# 08_-CAN_INTERPOSER.net
KiCad netlist of a schematic drawn in Altium Designer
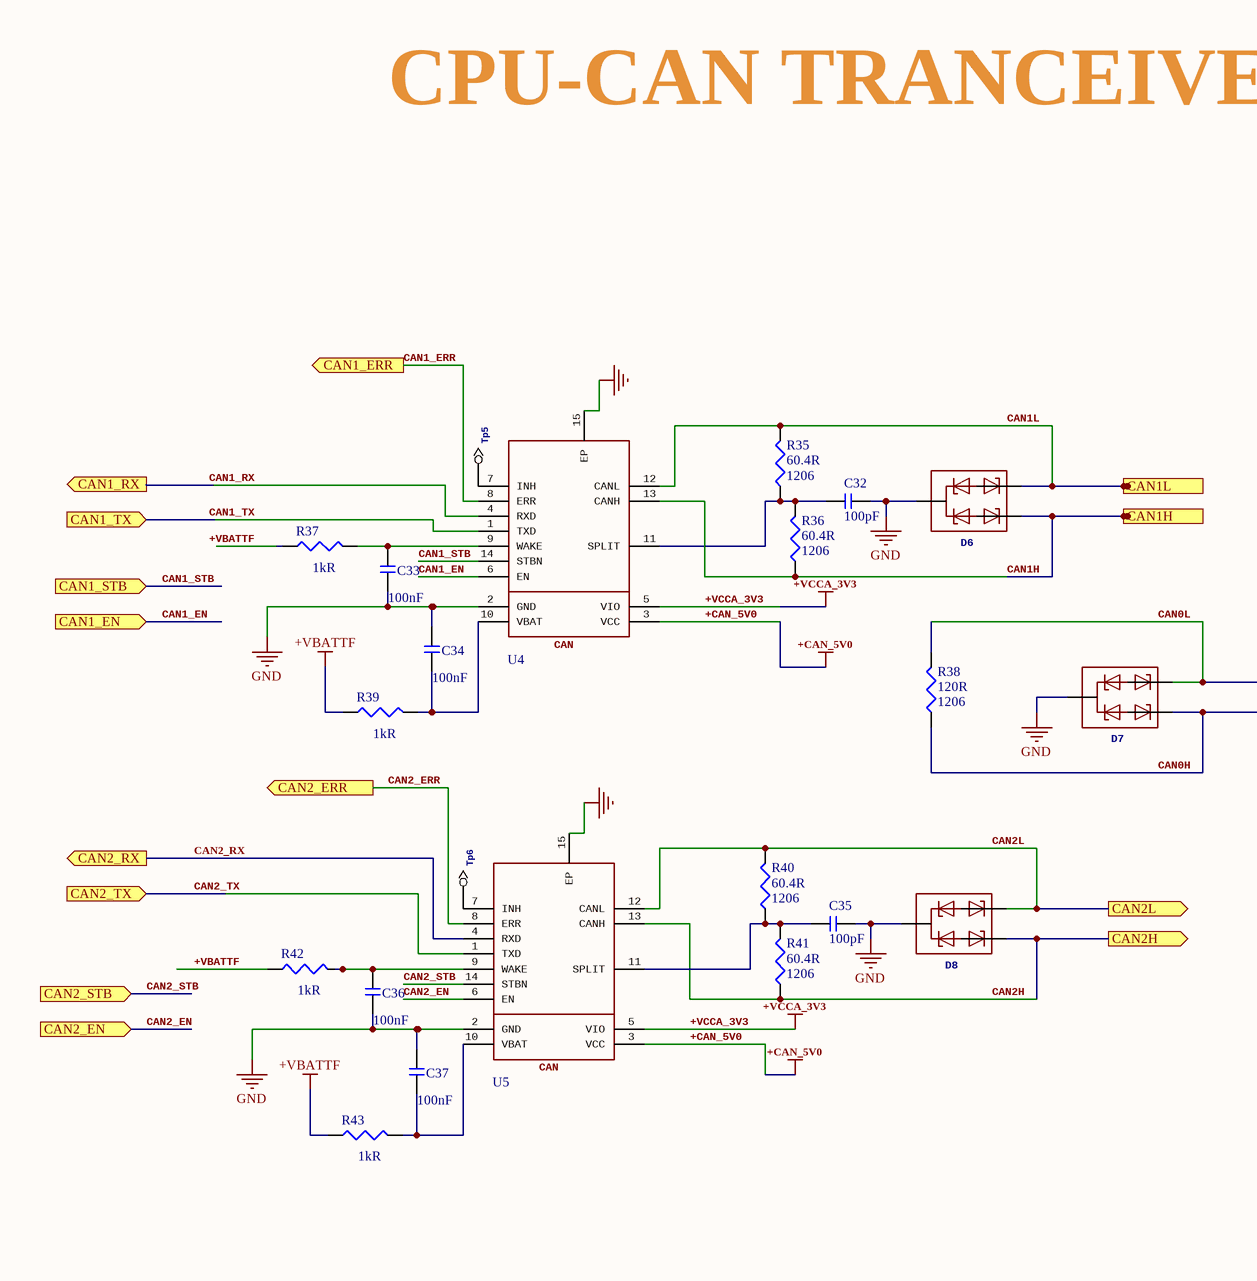
[diagram p0: [08]-CAN,INTERPOSER.SchDoc, left]
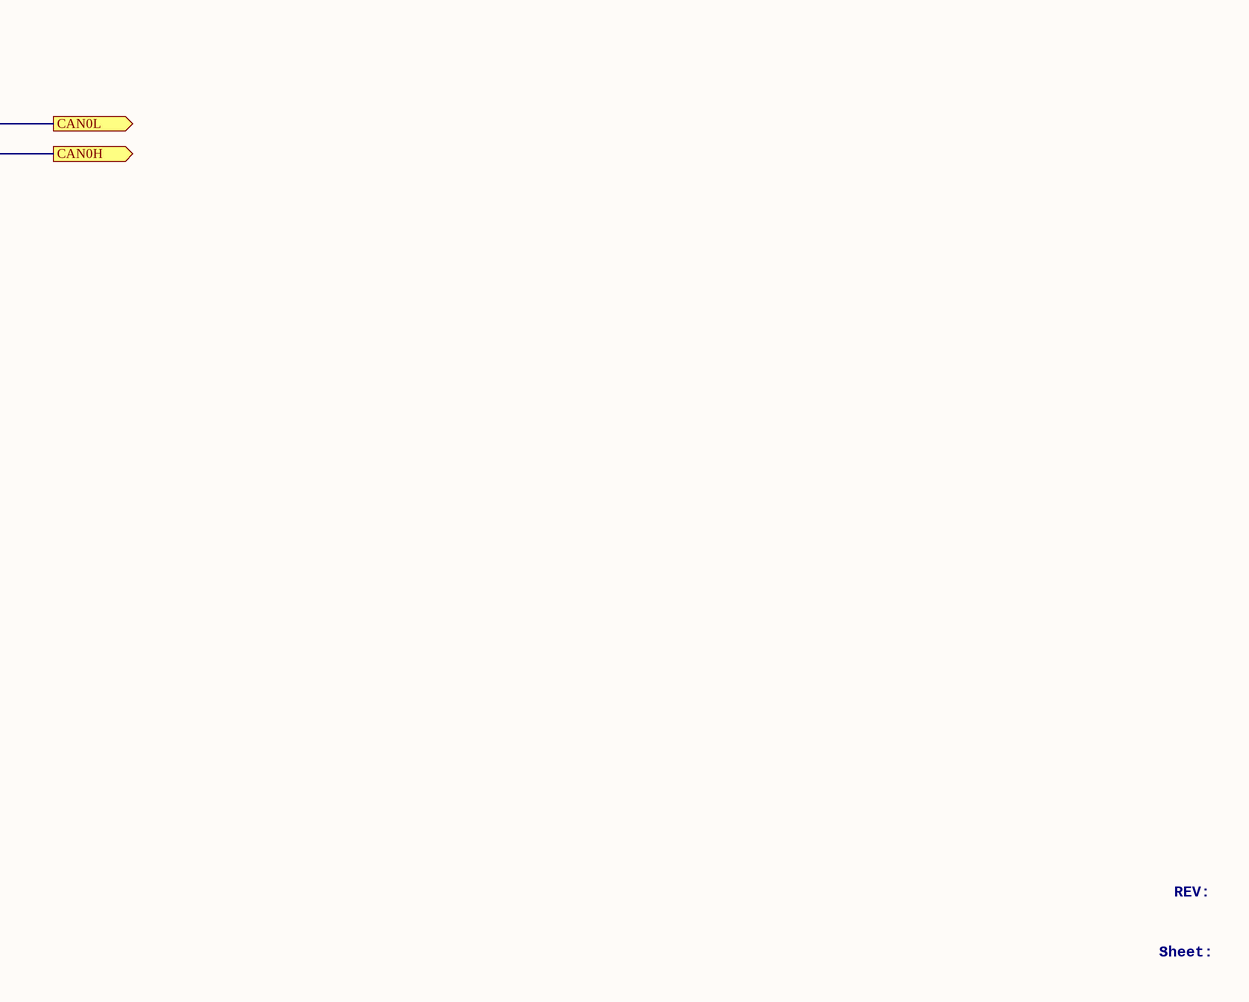
[diagram p1: [08]-CAN,INTERPOSER.SchDoc, right]

(export (version "E")
  (design (tool "Eeschema 10.0.6"))
  (components
    (comp (ref "C32")
      (value "GCM1555C1H101JA16D")
      (footprint "CAP0402")
      (description "0402 100 pF 50 V ±5 % Tolerance C0G SMT Multilayer Ceramic Capacitor")
      (fields
        (field (name "MANUFACTURER") "Murata")
        (field (name "TOLERANCE") "5%")
        (field (name "CAPACITANCE") "100pF")
      )
      (libsource (lib "altium-import") (part "root_1_GCM1555C1H101JA16D_"))
    )
    (comp (ref "C33")
      (value "GCM155R71C104KA55D")
      (footprint "CAP0402")
      (description "Multilayer Ceramic Capacitors (MLCC) - SMD/SMT 0402 0.1uF 16volts X7R 10%")
      (fields
        (field (name "MANUFACTURER") "Murata")
        (field (name "TOLERANCE") "10%")
        (field (name "CAPACITANCE") "100nF")
      )
      (libsource (lib "altium-import") (part "root_0_GCM155R71C104KA55D_"))
    )
    (comp (ref "C34")
      (value "GCM155R71C104KA55D")
      (footprint "CAP0402")
      (description "Multilayer Ceramic Capacitors (MLCC) - SMD/SMT 0402 0.1uF 16volts X7R 10%")
      (fields
        (field (name "MANUFACTURER") "Murata")
        (field (name "TOLERANCE") "10%")
        (field (name "CAPACITANCE") "100nF")
      )
      (libsource (lib "altium-import") (part "root_0_GCM155R71C104KA55D_"))
    )
    (comp (ref "C35")
      (value "GCM1555C1H101JA16D")
      (footprint "CAP0402")
      (description "0402 100 pF 50 V ±5 % Tolerance C0G SMT Multilayer Ceramic Capacitor")
      (fields
        (field (name "MANUFACTURER") "Murata")
        (field (name "TOLERANCE") "5%")
        (field (name "CAPACITANCE") "100pF")
      )
      (libsource (lib "altium-import") (part "root_1_GCM1555C1H101JA16D_"))
    )
    (comp (ref "C36")
      (value "GCM155R71C104KA55D")
      (footprint "CAP0402")
      (description "Multilayer Ceramic Capacitors (MLCC) - SMD/SMT 0402 0.1uF 16volts X7R 10%")
      (fields
        (field (name "MANUFACTURER") "Murata")
        (field (name "TOLERANCE") "10%")
        (field (name "CAPACITANCE") "100nF")
      )
      (libsource (lib "altium-import") (part "root_0_GCM155R71C104KA55D_"))
    )
    (comp (ref "C37")
      (value "GCM155R71C104KA55D")
      (footprint "CAP0402")
      (description "Multilayer Ceramic Capacitors (MLCC) - SMD/SMT 0402 0.1uF 16volts X7R 10%")
      (fields
        (field (name "MANUFACTURER") "Murata")
        (field (name "TOLERANCE") "10%")
        (field (name "CAPACITANCE") "100nF")
      )
      (libsource (lib "altium-import") (part "root_0_GCM155R71C104KA55D_"))
    )
    (comp (ref "D6")
      (value "PESD1CAN-U")
      (footprint "PESD1CAN-U_SOT323")
      (fields (field (name "MF") "NXP Semiconductors"))
      (libsource (lib "WeOnReferenceBoard") (part "PESD1CAN-U"))
    )
    (comp (ref "D7")
      (value "PESD1CAN-U")
      (footprint "PESD1CAN-U_SOT323")
      (fields (field (name "MF") "NXP Semiconductors"))
      (libsource (lib "WeOnReferenceBoard") (part "PESD1CAN-U"))
    )
    (comp (ref "D8")
      (value "PESD1CAN-U")
      (footprint "PESD1CAN-U_SOT323")
      (fields (field (name "MF") "NXP Semiconductors"))
      (libsource (lib "WeOnReferenceBoard") (part "PESD1CAN-U"))
    )
    (comp (ref "R35")
      (value "RMCF1206FT60R4")
      (description "Res Thick Film 1206 60.4 Ohm 1% 0.25W(1/4W) ±100ppm/C Pad SMD Automotive T/R")
      (fields
        (field (name "MANUFACTURER") "Stackpole Electronics")
        (field (name "TOLERANCE") "1%")
        (field (name "RESISTANCE") "60.4R")
        (field (name "CASE CODE (IMPERIAL)") "1206")
      )
      (libsource (lib "altium-import") (part "root_1_RMCF1206FT60R4_"))
    )
    (comp (ref "R36")
      (value "RMCF1206FT60R4")
      (description "Res Thick Film 1206 60.4 Ohm 1% 0.25W(1/4W) ±100ppm/C Pad SMD Automotive T/R")
      (fields
        (field (name "MANUFACTURER") "Stackpole Electronics")
        (field (name "TOLERANCE") "1%")
        (field (name "RESISTANCE") "60.4R")
        (field (name "CASE CODE (IMPERIAL)") "1206")
      )
      (libsource (lib "altium-import") (part "root_1_RMCF1206FT60R4_"))
    )
    (comp (ref "R37")
      (value "ERJ-2GEJ102X")
      (footprint "RES0402")
      (description "Res Thick Film 0402 1K Ohm 5% 1/10W ±200ppm/°C Molded SMD SMD Punched Carrier T/R")
      (fields
        (field (name "MANUFACTURER") "Panasonic")
        (field (name "TOLERANCE") "5%")
        (field (name "RESISTANCE") "1kR")
      )
      (libsource (lib "WeOnReferenceBoard") (part "ERJ-2GEJ102X"))
    )
    (comp (ref "R38")
      (value "RMCF1206JT120R")
      (description "Res Thick Film 1206 120 Ohm 5% 0.25W(1/4W) ±200ppm/C Pad SMD Automotive T/R")
      (fields
        (field (name "MANUFACTURER") "Stackpole Electronics")
        (field (name "TOLERANCE") "5%")
        (field (name "RESISTANCE") "120R")
        (field (name "CASE/PACKAGE") "1206")
      )
      (libsource (lib "altium-import") (part "root_1_RMCF1206JT120R_"))
    )
    (comp (ref "R39")
      (value "ERJ-2GEJ102X")
      (footprint "RES0402")
      (description "Res Thick Film 0402 1K Ohm 5% 1/10W ±200ppm/°C Molded SMD SMD Punched Carrier T/R")
      (fields
        (field (name "MANUFACTURER") "Panasonic")
        (field (name "TOLERANCE") "5%")
        (field (name "RESISTANCE") "1kR")
      )
      (libsource (lib "WeOnReferenceBoard") (part "ERJ-2GEJ102X"))
    )
    (comp (ref "R40")
      (value "RMCF1206FT60R4")
      (description "Res Thick Film 1206 60.4 Ohm 1% 0.25W(1/4W) ±100ppm/C Pad SMD Automotive T/R")
      (fields
        (field (name "MANUFACTURER") "Stackpole Electronics")
        (field (name "TOLERANCE") "1%")
        (field (name "RESISTANCE") "60.4R")
        (field (name "CASE CODE (IMPERIAL)") "1206")
      )
      (libsource (lib "altium-import") (part "root_1_RMCF1206FT60R4_"))
    )
    (comp (ref "R41")
      (value "RMCF1206FT60R4")
      (description "Res Thick Film 1206 60.4 Ohm 1% 0.25W(1/4W) ±100ppm/C Pad SMD Automotive T/R")
      (fields
        (field (name "MANUFACTURER") "Stackpole Electronics")
        (field (name "TOLERANCE") "1%")
        (field (name "RESISTANCE") "60.4R")
        (field (name "CASE CODE (IMPERIAL)") "1206")
      )
      (libsource (lib "altium-import") (part "root_1_RMCF1206FT60R4_"))
    )
    (comp (ref "R42")
      (value "ERJ-2GEJ102X")
      (footprint "RES0402")
      (description "Res Thick Film 0402 1K Ohm 5% 1/10W ±200ppm/°C Molded SMD SMD Punched Carrier T/R")
      (fields
        (field (name "MANUFACTURER") "Panasonic")
        (field (name "TOLERANCE") "5%")
        (field (name "RESISTANCE") "1kR")
      )
      (libsource (lib "WeOnReferenceBoard") (part "ERJ-2GEJ102X"))
    )
    (comp (ref "R43")
      (value "ERJ-2GEJ102X")
      (footprint "RES0402")
      (description "Res Thick Film 0402 1K Ohm 5% 1/10W ±200ppm/°C Molded SMD SMD Punched Carrier T/R")
      (fields
        (field (name "MANUFACTURER") "Panasonic")
        (field (name "TOLERANCE") "5%")
        (field (name "RESISTANCE") "1kR")
      )
      (libsource (lib "WeOnReferenceBoard") (part "ERJ-2GEJ102X"))
    )
    (comp (ref "Tp5")
      (value "TP")
      (footprint "TestPoint")
      (libsource (lib "altium-import") (part "root_1_TP_"))
    )
    (comp (ref "Tp6")
      (value "TP")
      (footprint "TestPoint")
      (libsource (lib "altium-import") (part "root_1_TP_"))
    )
    (comp (ref "U4")
      (value "WEON_TJA1043TK")
      (footprint "WEON_DFN-14_DE")
      (libsource (lib "WeOnReferenceBoard") (part "WEON_TJA1043TK"))
    )
    (comp (ref "U5")
      (value "WEON_TJA1043TK")
      (footprint "WEON_DFN-14_DE")
      (libsource (lib "WeOnReferenceBoard") (part "WEON_TJA1043TK"))
    )
  )
  (nets
    (net (code "1") (name "+CAN_5V0") (class "Default")
      (node (ref "U4") (pin "3") (pinfunction "VCC_3") (pintype "passive"))
      (node (ref "U5") (pin "3") (pinfunction "VCC_3") (pintype "passive"))
    )
    (net (code "2") (name "+VBATTF") (class "Default")
      (node (ref "R39") (pin "1") (pinfunction "1_1") (pintype "passive"))
      (node (ref "R42") (pin "1") (pinfunction "1_1") (pintype "passive"))
      (node (ref "R43") (pin "1") (pinfunction "1_1") (pintype "passive"))
    )
    (net (code "3") (name "+VCCA_3V3") (class "Default")
      (node (ref "U4") (pin "5") (pinfunction "VIO_5") (pintype "passive"))
      (node (ref "U5") (pin "5") (pinfunction "VIO_5") (pintype "passive"))
    )
    (net (code "4") (name "/CAN0H") (class "Default")
      (node (ref "D7") (pin "2") (pinfunction "K2_2") (pintype "passive"))
      (node (ref "R38") (pin "1") (pinfunction "1_1") (pintype "passive"))
    )
    (net (code "5") (name "/CAN0L") (class "Default")
      (node (ref "D7") (pin "1") (pinfunction "K1_1") (pintype "passive"))
      (node (ref "R38") (pin "2") (pinfunction "2_2") (pintype "passive"))
    )
    (net (code "6") (name "/CAN1H") (class "Default")
      (node (ref "D6") (pin "2") (pinfunction "K2_2") (pintype "passive"))
      (node (ref "R36") (pin "1") (pinfunction "1_1") (pintype "passive"))
      (node (ref "U4") (pin "13") (pinfunction "CANH_13") (pintype "passive"))
    )
    (net (code "7") (name "/CAN1L") (class "Default")
      (node (ref "D6") (pin "1") (pinfunction "K1_1") (pintype "passive"))
      (node (ref "R35") (pin "2") (pinfunction "2_2") (pintype "passive"))
      (node (ref "U4") (pin "12") (pinfunction "CANL_12") (pintype "passive"))
    )
    (net (code "8") (name "/CAN1_EN") (class "Default")
      (node (ref "U4") (pin "6") (pinfunction "EN_6") (pintype "passive"))
    )
    (net (code "9") (name "/CAN1_ERR") (class "Default")
      (node (ref "U4") (pin "8") (pinfunction "ERR_8") (pintype "passive"))
    )
    (net (code "10") (name "/CAN1_RX") (class "Default")
      (node (ref "U4") (pin "4") (pinfunction "RXD_4") (pintype "passive"))
    )
    (net (code "11") (name "/CAN1_STB") (class "Default")
      (node (ref "U4") (pin "14") (pinfunction "STBN_14") (pintype "passive"))
    )
    (net (code "12") (name "/CAN1_TX") (class "Default")
      (node (ref "U4") (pin "1") (pinfunction "TXD_1") (pintype "passive"))
    )
    (net (code "13") (name "/CAN2H") (class "Default")
      (node (ref "D8") (pin "2") (pinfunction "K2_2") (pintype "passive"))
      (node (ref "R41") (pin "1") (pinfunction "1_1") (pintype "passive"))
      (node (ref "U5") (pin "13") (pinfunction "CANH_13") (pintype "passive"))
    )
    (net (code "14") (name "/CAN2L") (class "Default")
      (node (ref "D8") (pin "1") (pinfunction "K1_1") (pintype "passive"))
      (node (ref "R40") (pin "2") (pinfunction "2_2") (pintype "passive"))
      (node (ref "U5") (pin "12") (pinfunction "CANL_12") (pintype "passive"))
    )
    (net (code "15") (name "/CAN2_EN") (class "Default")
      (node (ref "U5") (pin "6") (pinfunction "EN_6") (pintype "passive"))
    )
    (net (code "16") (name "/CAN2_ERR") (class "Default")
      (node (ref "U5") (pin "8") (pinfunction "ERR_8") (pintype "passive"))
    )
    (net (code "17") (name "/CAN2_RX") (class "Default")
      (node (ref "U5") (pin "4") (pinfunction "RXD_4") (pintype "passive"))
    )
    (net (code "18") (name "/CAN2_STB") (class "Default")
      (node (ref "U5") (pin "14") (pinfunction "STBN_14") (pintype "passive"))
    )
    (net (code "19") (name "/CAN2_TX") (class "Default")
      (node (ref "U5") (pin "1") (pinfunction "TXD_1") (pintype "passive"))
    )
    (net (code "20") (name "GND") (class "Default")
      (node (ref "C32") (pin "2") (pinfunction "2_2") (pintype "passive"))
      (node (ref "C33") (pin "2") (pinfunction "2_2") (pintype "passive"))
      (node (ref "C34") (pin "1") (pinfunction "1_1") (pintype "passive"))
      (node (ref "C35") (pin "2") (pinfunction "2_2") (pintype "passive"))
      (node (ref "C36") (pin "2") (pinfunction "2_2") (pintype "passive"))
      (node (ref "C37") (pin "1") (pinfunction "1_1") (pintype "passive"))
      (node (ref "D6") (pin "3") (pinfunction "CK_3") (pintype "passive"))
      (node (ref "D7") (pin "3") (pinfunction "CK_3") (pintype "passive"))
      (node (ref "D8") (pin "3") (pinfunction "CK_3") (pintype "passive"))
      (node (ref "U4") (pin "15") (pinfunction "EP_15") (pintype "passive"))
      (node (ref "U4") (pin "2") (pinfunction "GND_2") (pintype "passive"))
      (node (ref "U5") (pin "15") (pinfunction "EP_15") (pintype "passive"))
      (node (ref "U5") (pin "2") (pinfunction "GND_2") (pintype "passive"))
    )
    (net (code "21") (name "Net-(U4-INH)") (class "Default")
      (node (ref "Tp5") (pin "1") (pinfunction "1_1") (pintype "passive"))
      (node (ref "U4") (pin "7") (pinfunction "INH_7") (pintype "passive"))
    )
    (net (code "22") (name "Net-(U4-SPLIT)") (class "Default")
      (node (ref "C32") (pin "1") (pinfunction "1_1") (pintype "passive"))
      (node (ref "R35") (pin "1") (pinfunction "1_1") (pintype "passive"))
      (node (ref "R36") (pin "2") (pinfunction "2_2") (pintype "passive"))
      (node (ref "U4") (pin "11") (pinfunction "SPLIT_11") (pintype "passive"))
    )
    (net (code "23") (name "Net-(U4-VBAT)") (class "Default")
      (node (ref "C34") (pin "2") (pinfunction "2_2") (pintype "passive"))
      (node (ref "R39") (pin "2") (pinfunction "2_2") (pintype "passive"))
      (node (ref "U4") (pin "10") (pinfunction "VBAT_10") (pintype "passive"))
    )
    (net (code "24") (name "Net-(U4-WAKE)") (class "Default")
      (node (ref "C33") (pin "1") (pinfunction "1_1") (pintype "passive"))
      (node (ref "R37") (pin "2") (pinfunction "2_2") (pintype "passive"))
      (node (ref "U4") (pin "9") (pinfunction "WAKE_9") (pintype "passive"))
    )
    (net (code "25") (name "Net-(U5-INH)") (class "Default")
      (node (ref "Tp6") (pin "1") (pinfunction "1_1") (pintype "passive"))
      (node (ref "U5") (pin "7") (pinfunction "INH_7") (pintype "passive"))
    )
    (net (code "26") (name "Net-(U5-SPLIT)") (class "Default")
      (node (ref "C35") (pin "1") (pinfunction "1_1") (pintype "passive"))
      (node (ref "R40") (pin "1") (pinfunction "1_1") (pintype "passive"))
      (node (ref "R41") (pin "2") (pinfunction "2_2") (pintype "passive"))
      (node (ref "U5") (pin "11") (pinfunction "SPLIT_11") (pintype "passive"))
    )
    (net (code "27") (name "Net-(U5-VBAT)") (class "Default")
      (node (ref "C37") (pin "2") (pinfunction "2_2") (pintype "passive"))
      (node (ref "R43") (pin "2") (pinfunction "2_2") (pintype "passive"))
      (node (ref "U5") (pin "10") (pinfunction "VBAT_10") (pintype "passive"))
    )
    (net (code "28") (name "Net-(U5-WAKE)") (class "Default")
      (node (ref "C36") (pin "1") (pinfunction "1_1") (pintype "passive"))
      (node (ref "R42") (pin "2") (pinfunction "2_2") (pintype "passive"))
      (node (ref "U5") (pin "9") (pinfunction "WAKE_9") (pintype "passive"))
    )
    (net (code "29") (name "unconnected-(R37-Pad1)") (class "Default")
      (node (ref "R37") (pin "1") (pinfunction "1_1") (pintype "passive"))
    )
  )
)
